# Heater_PCB_Column_Coil.net
KiCad netlist of a schematic drawn in Altium Designer
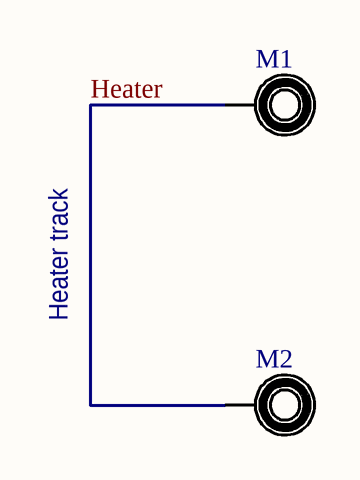
[diagram p0: Heater PCB Column Coil.SchDoc]

(export (version "E")
  (design (tool "Eeschema 10.0.6"))
  (components
    (comp (ref "M1")
      (value "PTH")
      (footprint "PTH-M3.4-D6.0")
      (description "Plated Through-Hole, M3.4, Round Pad 6mm")
      (fields (field (name "MANUFACTURER") "mechanical"))
      (libsource (lib "AECDB") (part "PTH"))
    )
    (comp (ref "M2")
      (value "PTH")
      (footprint "PTH-M3.4-D6.0")
      (description "Plated Through-Hole, M3.4, Round Pad 6mm")
      (fields (field (name "MANUFACTURER") "mechanical"))
      (libsource (lib "AECDB") (part "PTH"))
    )
  )
  (nets
    (net (code "1") (name "/Heater") (class "Default")
      (node (ref "M1") (pin "1") (pinfunction "1_1") (pintype "passive"))
      (node (ref "M2") (pin "1") (pinfunction "1_1") (pintype "passive"))
    )
  )
)
